# debug-board.net
KiCad netlist of a schematic drawn in EAGLE
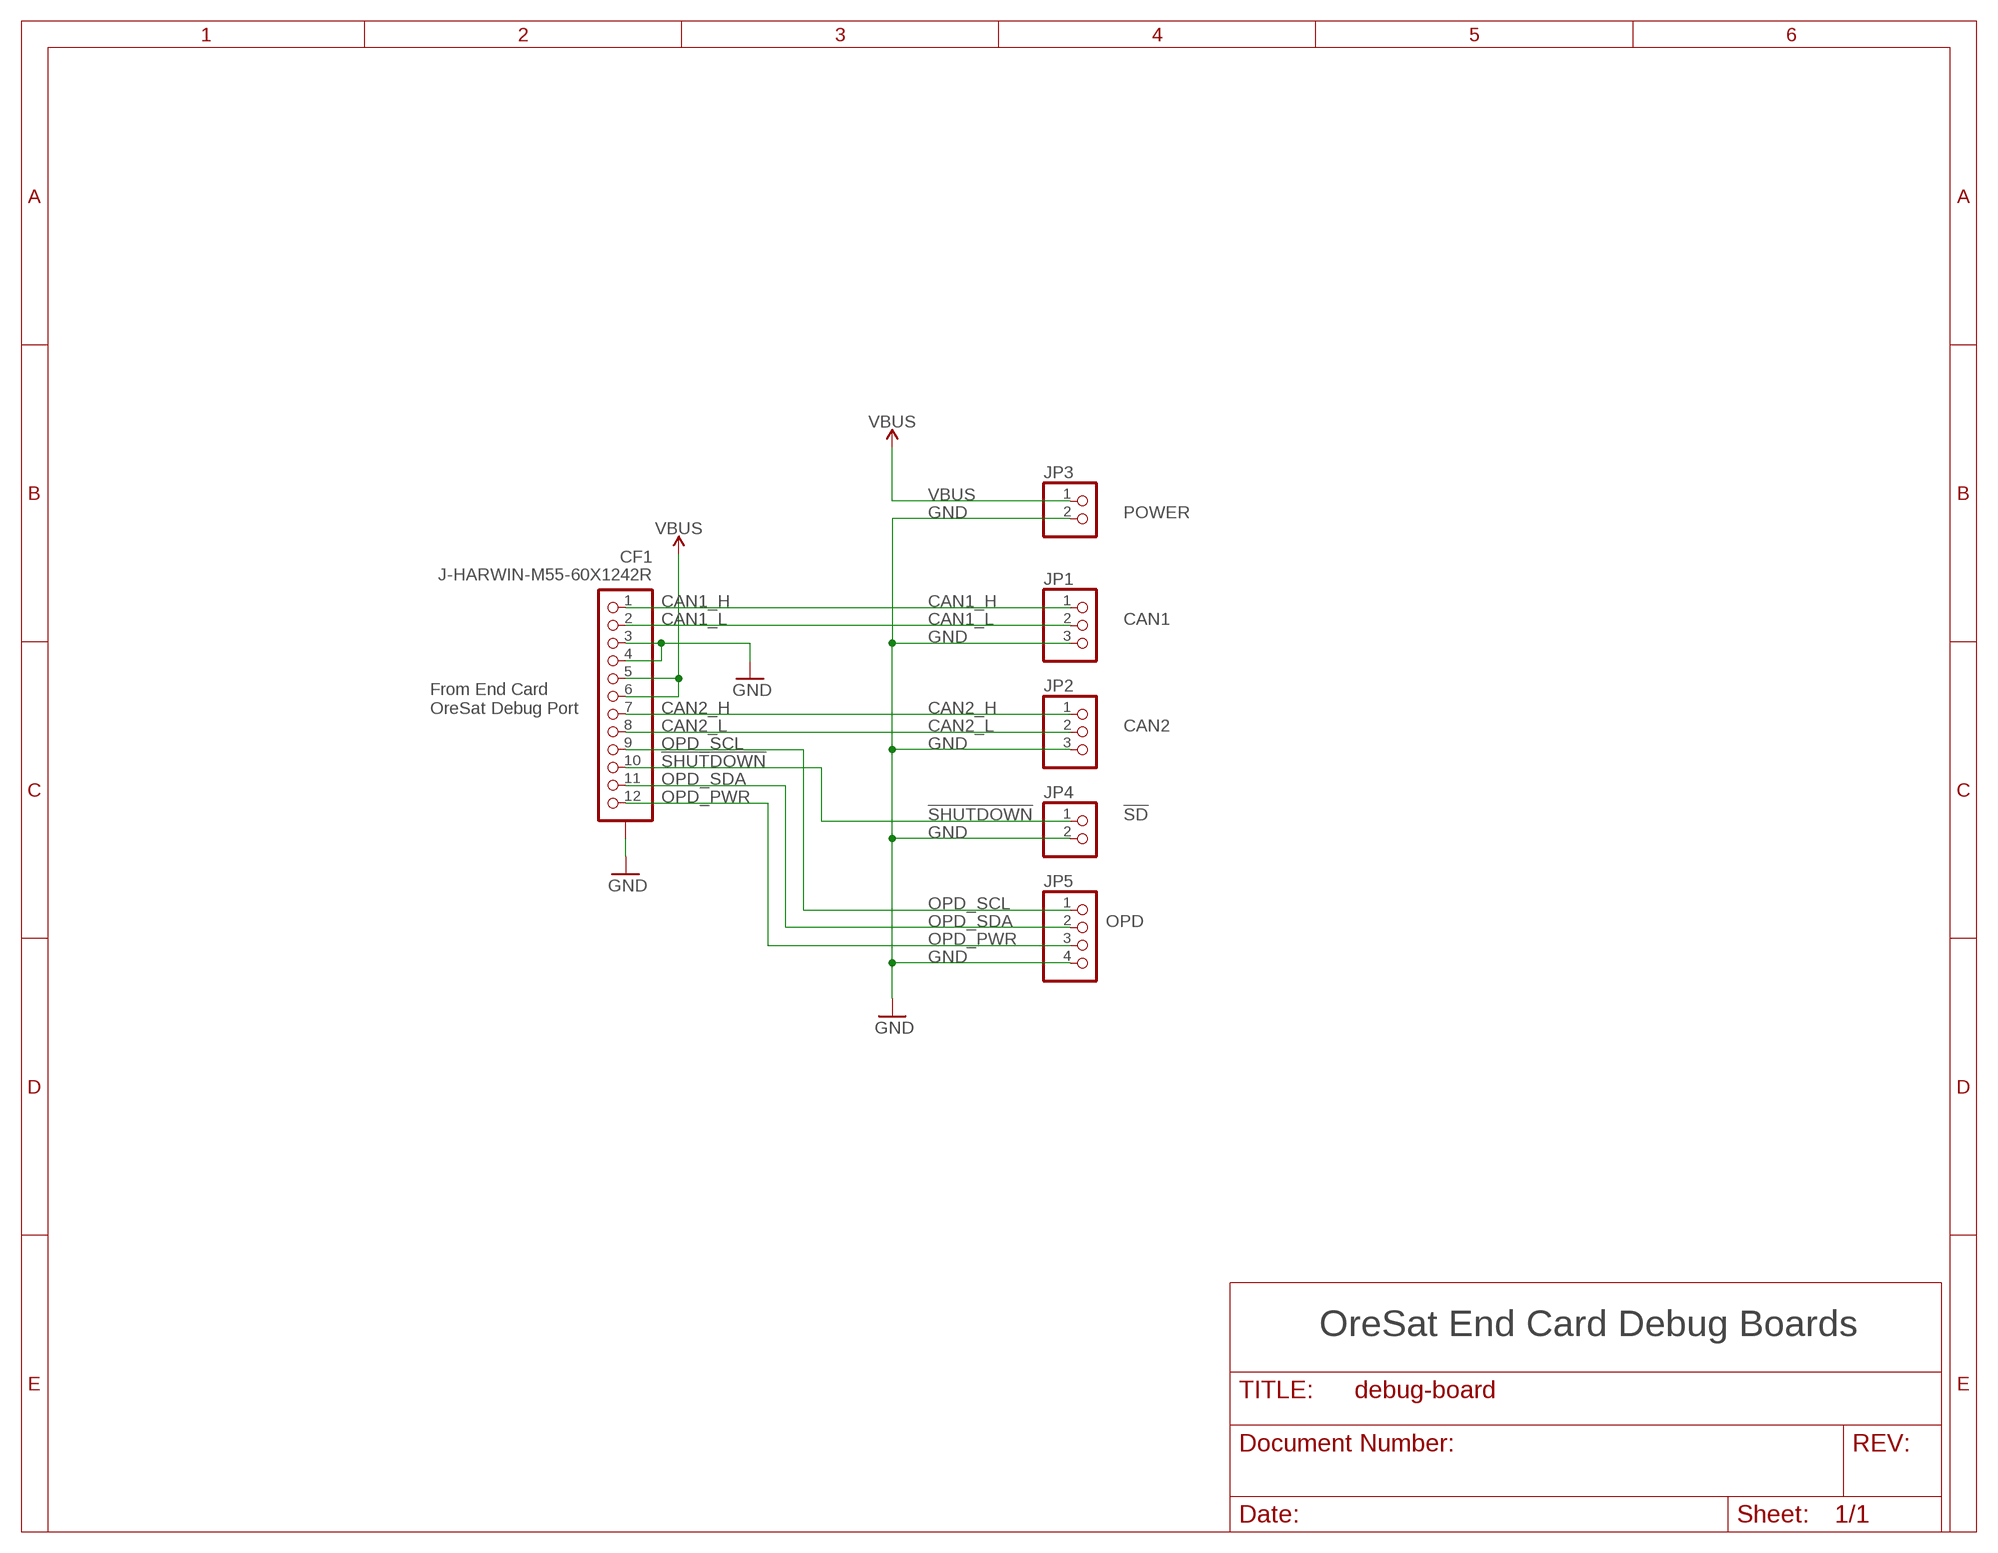
[diagram p0: schematic, sheet 1]

(export (version "E")
  (design (tool "Eeschema 10.0.6"))
  (components
    (comp (ref "CF1")
      (value "J-HARWIN-M55-60X1242R")
      (footprint "eagle-import:HARWIN-M55-60X1242R")
      (libsource (lib "eagle-import") (part "J-HARWIN-M55-60X1242R"))
    )
    (comp (ref "JP1")
      (value "PINHD-1X3")
      (footprint "eagle-import:1X03")
      (libsource (lib "eagle-import") (part "PINHD-1X3"))
    )
    (comp (ref "JP2")
      (value "PINHD-1X3")
      (footprint "eagle-import:1X03")
      (libsource (lib "eagle-import") (part "PINHD-1X3"))
    )
    (comp (ref "JP3")
      (value "PINHD-1X2")
      (footprint "eagle-import:1X02")
      (libsource (lib "eagle-import") (part "PINHD-1X2"))
    )
    (comp (ref "JP4")
      (value "PINHD-1X2")
      (footprint "eagle-import:1X02")
      (libsource (lib "eagle-import") (part "PINHD-1X2"))
    )
    (comp (ref "JP5")
      (value "PINHD-1X4")
      (footprint "eagle-import:1X04")
      (libsource (lib "eagle-import") (part "PINHD-1X4"))
    )
  )
  (nets
    (net (code "1") (name "/CAN1_H") (class "Default")
      (node (ref "CF1") (pin "1") (pinfunction "1_1") (pintype "passive"))
      (node (ref "JP1") (pin "1") (pinfunction "1_1") (pintype "passive"))
    )
    (net (code "2") (name "/CAN1_L") (class "Default")
      (node (ref "CF1") (pin "2") (pinfunction "2_2") (pintype "passive"))
      (node (ref "JP1") (pin "2") (pinfunction "2_2") (pintype "passive"))
    )
    (net (code "3") (name "/CAN2_H") (class "Default")
      (node (ref "CF1") (pin "7") (pinfunction "7_7") (pintype "passive"))
      (node (ref "JP2") (pin "1") (pinfunction "1_1") (pintype "passive"))
    )
    (net (code "4") (name "/CAN2_L") (class "Default")
      (node (ref "CF1") (pin "8") (pinfunction "8_8") (pintype "passive"))
      (node (ref "JP2") (pin "2") (pinfunction "2_2") (pintype "passive"))
    )
    (net (code "5") (name "/OPD_PWR") (class "Default")
      (node (ref "CF1") (pin "12") (pinfunction "12_12") (pintype "passive"))
      (node (ref "JP5") (pin "3") (pinfunction "3_3") (pintype "passive"))
    )
    (net (code "6") (name "/OPD_SCL") (class "Default")
      (node (ref "CF1") (pin "9") (pinfunction "9_9") (pintype "passive"))
      (node (ref "JP5") (pin "1") (pinfunction "1_1") (pintype "passive"))
    )
    (net (code "7") (name "/OPD_SDA") (class "Default")
      (node (ref "CF1") (pin "11") (pinfunction "11_11") (pintype "passive"))
      (node (ref "JP5") (pin "2") (pinfunction "2_2") (pintype "passive"))
    )
    (net (code "8") (name "/~{SHUTDOWN}") (class "Default")
      (node (ref "CF1") (pin "10") (pinfunction "10_10") (pintype "passive"))
      (node (ref "JP4") (pin "1") (pinfunction "1_1") (pintype "passive"))
    )
    (net (code "9") (name "GND") (class "Default")
      (node (ref "CF1") (pin "3") (pinfunction "3_3") (pintype "passive"))
      (node (ref "CF1") (pin "4") (pinfunction "4_4") (pintype "passive"))
      (node (ref "CF1") (pin "P$1") (pinfunction "SHIELDS_P$1") (pintype "passive"))
      (node (ref "CF1") (pin "P$2") (pinfunction "SHIELDS_P$2") (pintype "passive"))
      (node (ref "CF1") (pin "P$3") (pinfunction "SHIELDS_P$3") (pintype "passive"))
      (node (ref "CF1") (pin "P$4") (pinfunction "SHIELDS_P$4") (pintype "passive"))
      (node (ref "JP1") (pin "3") (pinfunction "3_3") (pintype "passive"))
      (node (ref "JP2") (pin "3") (pinfunction "3_3") (pintype "passive"))
      (node (ref "JP3") (pin "2") (pinfunction "2_2") (pintype "passive"))
      (node (ref "JP4") (pin "2") (pinfunction "2_2") (pintype "passive"))
      (node (ref "JP5") (pin "4") (pinfunction "4_4") (pintype "passive"))
    )
    (net (code "10") (name "VBUS") (class "Default")
      (node (ref "CF1") (pin "5") (pinfunction "5_5") (pintype "passive"))
      (node (ref "CF1") (pin "6") (pinfunction "6_6") (pintype "passive"))
      (node (ref "JP3") (pin "1") (pinfunction "1_1") (pintype "passive"))
    )
  )
)
